# CAN_Sheet.net
KiCad netlist of a schematic drawn in Altium Designer
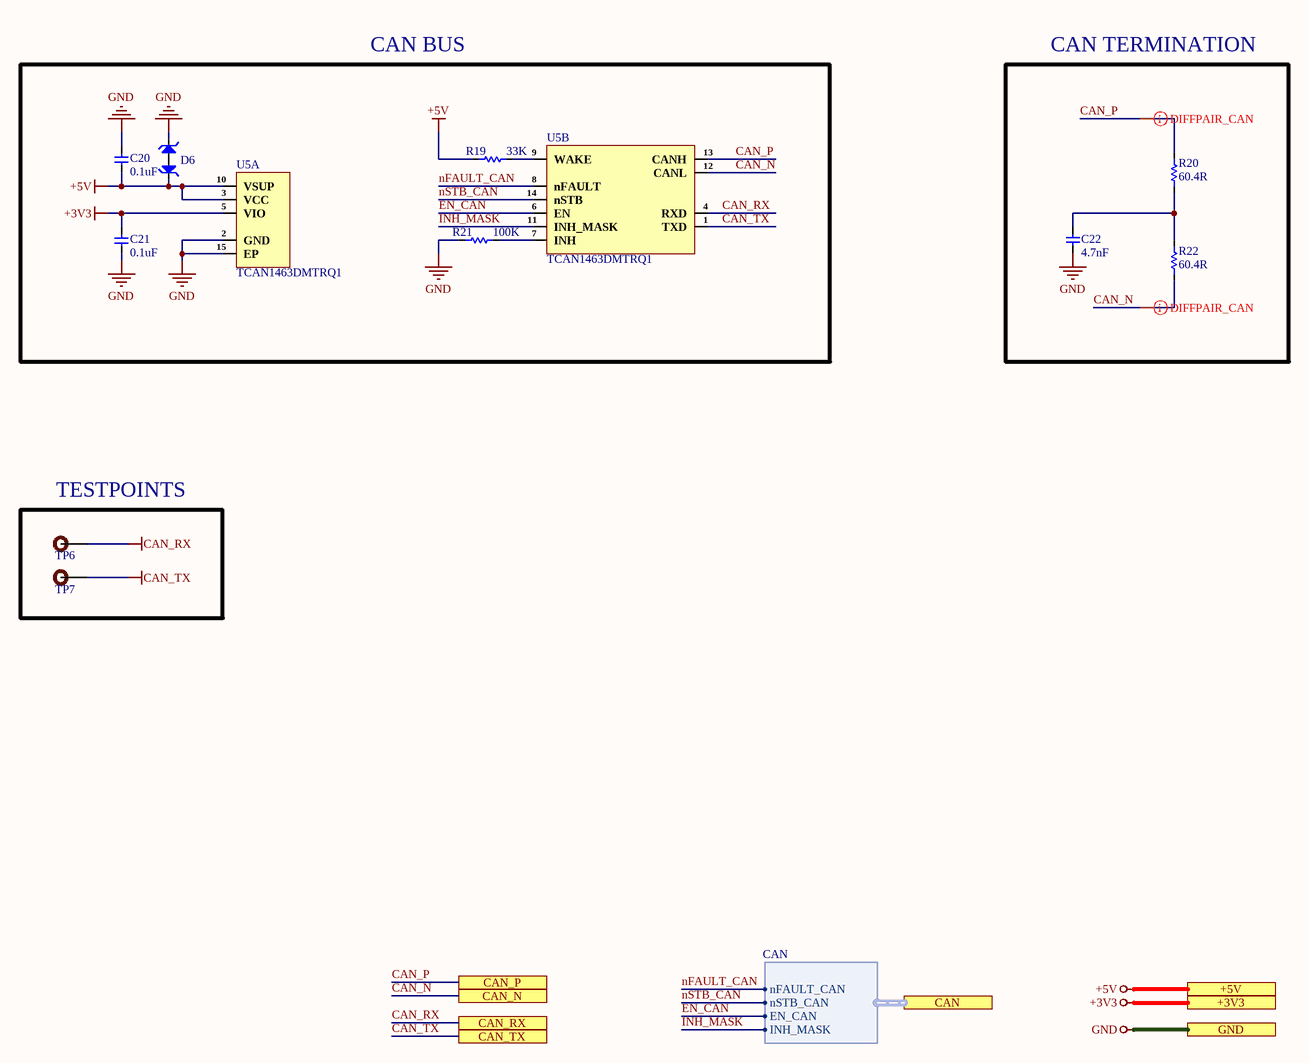
[diagram p0: CAN_Sheet.SchDoc]

(export (version "E")
  (design (tool "Eeschema 10.0.6"))
  (components
    (comp (ref "C20")
      (value "0.1uF")
      (footprint "Cap-0402")
      (description "CAP CER 0.1UF 16V X7R 0402")
      (fields
        (field (name "MANUFACTURER") "Yageo")
        (field (name "MANUFACTURER PART NUMBER") "CC0402JRX7R7BB104")
      )
      (libsource (lib "eSpark Libraries") (part "CC0402JRX7R7BB104"))
    )
    (comp (ref "C21")
      (value "0.1uF")
      (footprint "Cap-0402")
      (description "CAP CER 0.1UF 16V X7R 0402")
      (fields
        (field (name "MANUFACTURER") "Yageo")
        (field (name "MANUFACTURER PART NUMBER") "CC0402JRX7R7BB104")
      )
      (libsource (lib "eSpark Libraries") (part "CC0402JRX7R7BB104"))
    )
    (comp (ref "C22")
      (value "4.7nF")
      (footprint "Cap-0402")
      (description "CAP CER 4700PF 50V X7R 0402")
      (fields
        (field (name "MANUFACTURER") "Yageo")
        (field (name "MANUFACTURER PART NUMBER") "CC0402KRX7R9BB472")
      )
      (libsource (lib "eSpark Libraries") (part "CC0402KRX7R9BB472"))
    )
    (comp (ref "D6")
      (value "PESD5V0H1BSFYL")
      (footprint "DSN0603-2")
      (description "TVS DIODE 5VWM 6.3VC DSN0603-2")
      (fields (field (name "MANUFACTURER") "Nexperia") (field (name "LCSC PART NUMBER") "C477989"))
      (libsource (lib "eSpark Libraries") (part "PESD5V0H1BSFYL"))
    )
    (comp (ref "R19")
      (value "33K")
      (footprint "Res-0402")
      (description "RES 33K OHM 1% 1/16W 0402")
      (fields
        (field (name "MANUFACTURER") "YAGEO")
        (field (name "MANUFACTURER PART NUMBER") "RC0402FR-0733KL")
      )
      (libsource (lib "eSpark Libraries") (part "RC0402FR-0733KL"))
    )
    (comp (ref "R20")
      (value "60.4R")
      (footprint "Res-0603")
      (description "100mW Thick Film Resistors ±100ppm/℃ ±1% 60.4Ω 0603 Chip Resistor - Surface Mount ROHS")
      (fields
        (field (name "MANUFACTURER PART NUMBER") "RTT0360R4FTP")
        (field (name "LCSC PART NUMBER") "C103744")
      )
      (libsource (lib "eSpark Libraries") (part "RTT0360R4FTP"))
    )
    (comp (ref "R21")
      (value "100K")
      (footprint "Res-0402")
      (description "RES 100K OHM 1% 1/16W 0402")
      (fields
        (field (name "MANUFACTURER") "Yageo")
        (field (name "MANUFACTURER PART NUMBER") "RC0402FR-07100KL")
      )
      (libsource (lib "eSpark Libraries") (part "RC0402FR-07100KL"))
    )
    (comp (ref "R22")
      (value "60.4R")
      (footprint "Res-0603")
      (description "100mW Thick Film Resistors ±100ppm/℃ ±1% 60.4Ω 0603 Chip Resistor - Surface Mount ROHS")
      (fields
        (field (name "MANUFACTURER PART NUMBER") "RTT0360R4FTP")
        (field (name "LCSC PART NUMBER") "C103744")
      )
      (libsource (lib "eSpark Libraries") (part "RTT0360R4FTP"))
    )
    (comp (ref "TP6")
      (value "TEST POINT")
      (footprint "Test-point")
      (description "Test Point ON")
      (libsource (lib "eSpark Libraries") (part "TEST POINT"))
    )
    (comp (ref "TP7")
      (value "TEST POINT")
      (footprint "Test-point")
      (description "Test Point ON")
      (libsource (lib "eSpark Libraries") (part "TEST POINT"))
    )
    (comp (ref "U5")
      (value "TCAN1463DMTRQ1")
      (footprint "VSON-14(3x4.5)")
      (description "IC TRANSCEIVER HALF 1/1 14VSON")
      (fields (field (name "MANUFACTURER") "Texas Instruments") (field (name "LCSC PART NUMBER") "C5215823"))
      (libsource (lib "eSpark Libraries") (part "TCAN1463DMTRQ1"))
    )
  )
  (nets
    (net (code "2") (name "+3V3") (class "Default")
      (node (ref "C21") (pin "2") (pinfunction "2_2") (pintype "passive"))
      (node (ref "U5") (pin "5") (pinfunction "VIO_5") (pintype "passive"))
    )
    (net (code "3") (name "+5V") (class "Default")
      (node (ref "C20") (pin "1") (pinfunction "1_1") (pintype "passive"))
      (node (ref "D6") (pin "1") (pinfunction "1_1") (pintype "passive"))
      (node (ref "R19") (pin "1") (pinfunction "1_1") (pintype "passive"))
      (node (ref "U5") (pin "10") (pinfunction "VSUP_10") (pintype "passive"))
      (node (ref "U5") (pin "3") (pinfunction "VCC_3") (pintype "passive"))
    )
    (net (code "4") (name "/CAN_N") (class "Default")
      (node (ref "R22") (pin "2") (pinfunction "2_2") (pintype "passive"))
      (node (ref "U5") (pin "12") (pinfunction "CANL_12") (pintype "passive"))
    )
    (net (code "5") (name "/CAN_P") (class "Default")
      (node (ref "R20") (pin "1") (pinfunction "1_1") (pintype "passive"))
      (node (ref "U5") (pin "13") (pinfunction "CANH_13") (pintype "passive"))
    )
    (net (code "6") (name "/EN_CAN") (class "Default")
      (node (ref "U5") (pin "6") (pinfunction "EN_6") (pintype "passive"))
    )
    (net (code "7") (name "/INH_MASK") (class "Default")
      (node (ref "U5") (pin "11") (pinfunction "INH_MASK_11") (pintype "passive"))
    )
    (net (code "8") (name "/nFAULT_CAN") (class "Default")
      (node (ref "U5") (pin "8") (pinfunction "nFAULT_8") (pintype "passive"))
    )
    (net (code "9") (name "/nSTB_CAN") (class "Default")
      (node (ref "U5") (pin "14") (pinfunction "nSTB_14") (pintype "passive"))
    )
    (net (code "11") (name "CAN_RX") (class "Default")
      (node (ref "TP6") (pin "1") (pinfunction "1_1") (pintype "passive"))
      (node (ref "U5") (pin "4") (pinfunction "RXD_4") (pintype "passive"))
    )
    (net (code "12") (name "CAN_TX") (class "Default")
      (node (ref "TP7") (pin "1") (pinfunction "1_1") (pintype "passive"))
      (node (ref "U5") (pin "1") (pinfunction "TXD_1") (pintype "passive"))
    )
    (net (code "13") (name "GND") (class "Default")
      (node (ref "C20") (pin "2") (pinfunction "2_2") (pintype "passive"))
      (node (ref "C21") (pin "1") (pinfunction "1_1") (pintype "passive"))
      (node (ref "C22") (pin "2") (pinfunction "2_2") (pintype "passive"))
      (node (ref "D6") (pin "2") (pinfunction "2_2") (pintype "passive"))
      (node (ref "R21") (pin "1") (pinfunction "1_1") (pintype "passive"))
      (node (ref "U5") (pin "15") (pinfunction "EP_15") (pintype "passive"))
      (node (ref "U5") (pin "2") (pinfunction "GND_2") (pintype "passive"))
    )
    (net (code "14") (name "Net-(C22-Pad1)") (class "Default")
      (node (ref "C22") (pin "1") (pinfunction "1_1") (pintype "passive"))
      (node (ref "R20") (pin "2") (pinfunction "2_2") (pintype "passive"))
      (node (ref "R22") (pin "1") (pinfunction "1_1") (pintype "passive"))
    )
    (net (code "15") (name "Net-(U5B-INH)") (class "Default")
      (node (ref "R21") (pin "2") (pinfunction "2_2") (pintype "passive"))
      (node (ref "U5") (pin "7") (pinfunction "INH_7") (pintype "passive"))
    )
    (net (code "16") (name "Net-(U5B-WAKE)") (class "Default")
      (node (ref "R19") (pin "2") (pinfunction "2_2") (pintype "passive"))
      (node (ref "U5") (pin "9") (pinfunction "WAKE_9") (pintype "passive"))
    )
  )
)
